# SparkFun_XBee_Development_Board.net
KiCad netlist of a schematic drawn in EAGLE
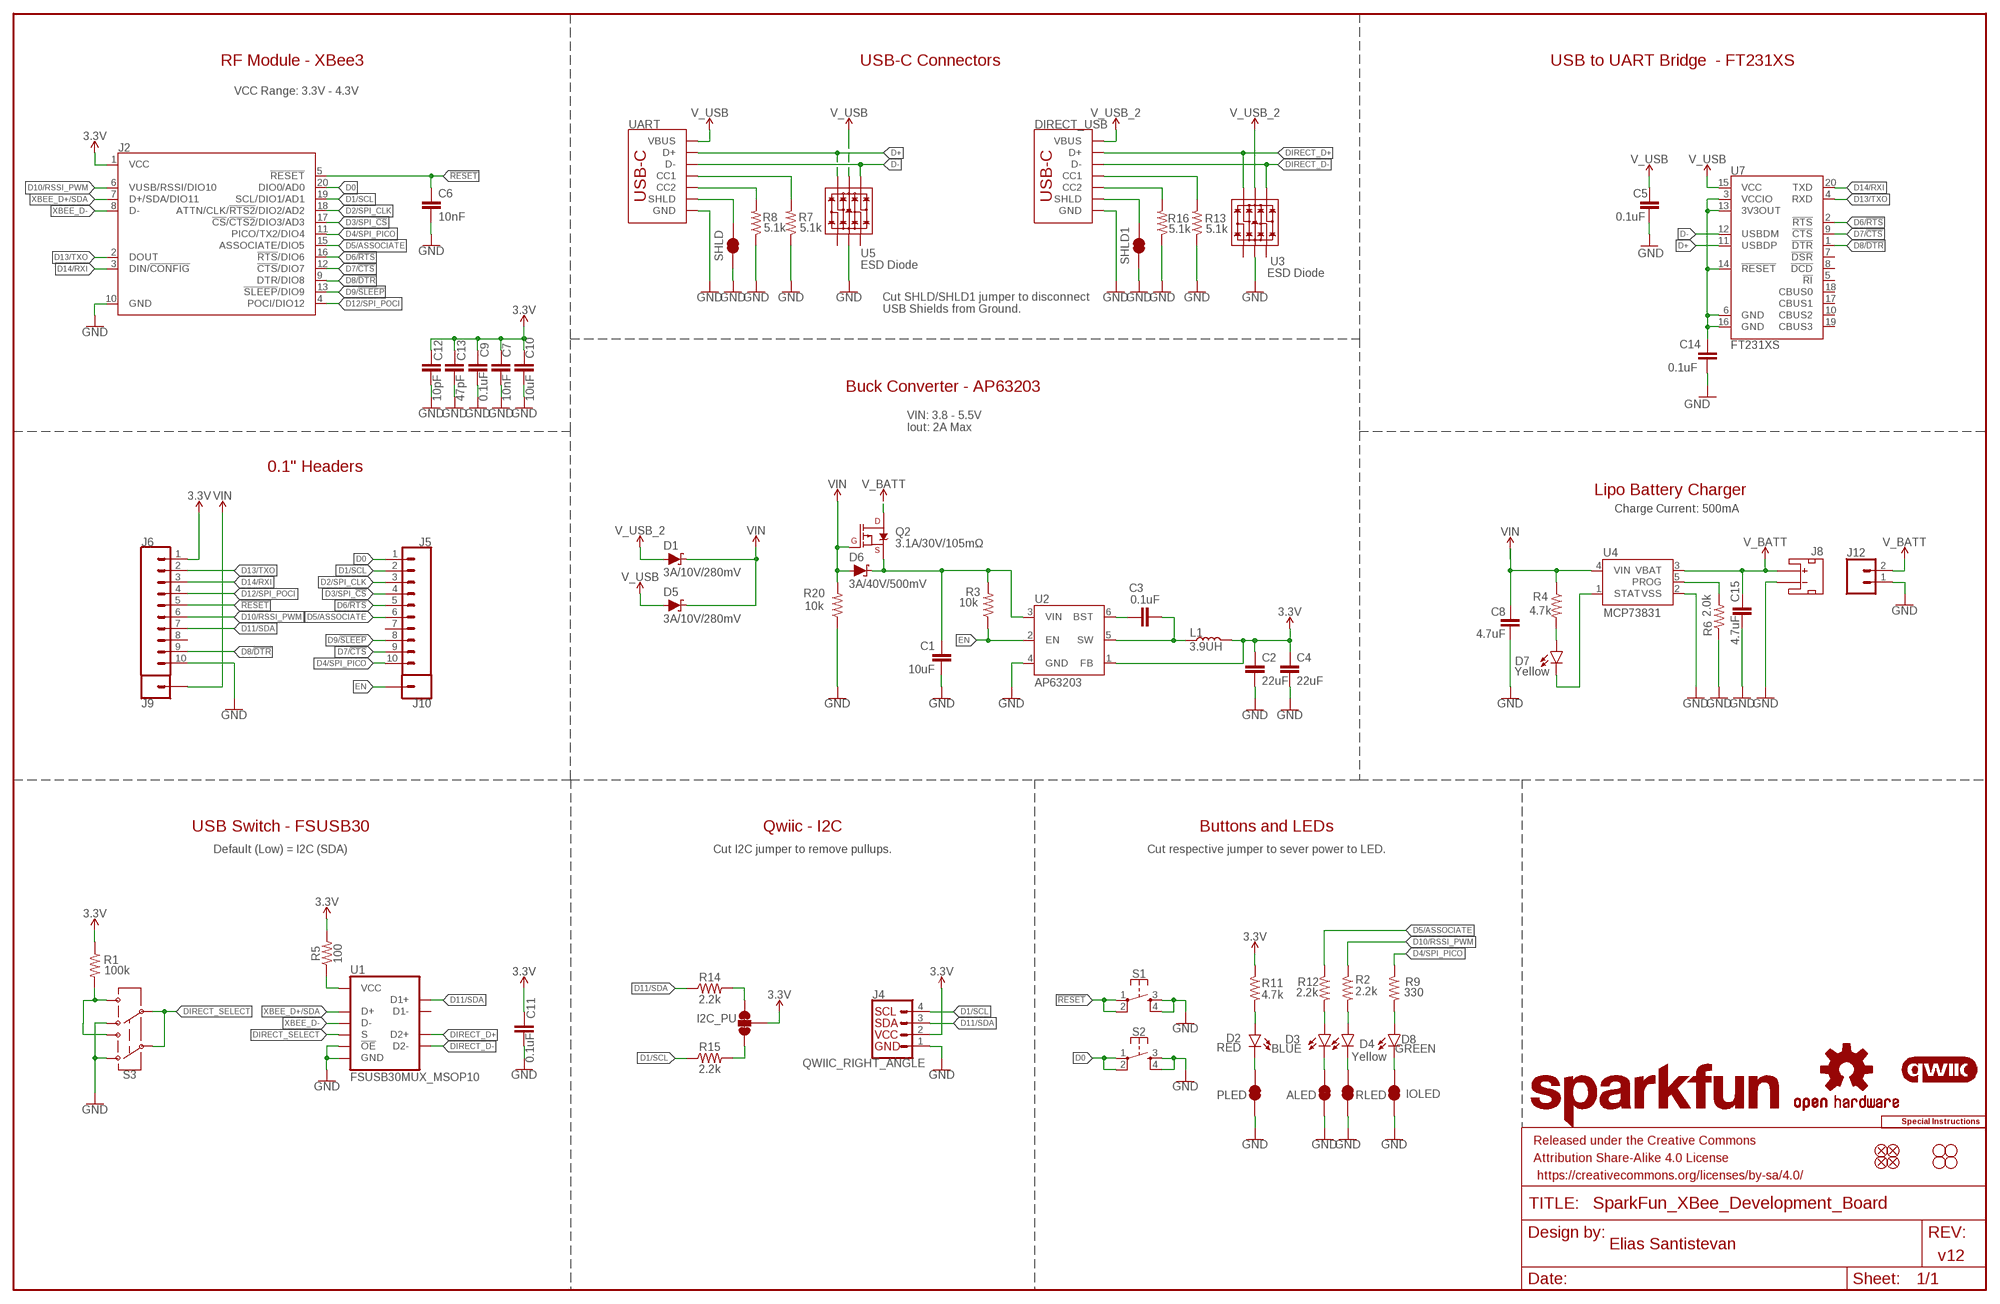
[diagram p0: schematic, sheet 1]

(export (version "E")
  (design (tool "Eeschema 10.0.6"))
  (components
    (comp (ref "ALED")
      (value "JUMPER-SMT_2_NC_TRACE_SILK")
      (footprint "eagle-import:SMT-JUMPER_2_NC_TRACE_SILK")
      (libsource (lib "eagle-import") (part "JUMPER-SMT_2_NC_TRACE_SILK"))
    )
    (comp (ref "C1")
      (value "10uF")
      (footprint "eagle-import:1210")
      (libsource (lib "eagle-import") (part "10UF-1210-50V-20%"))
    )
    (comp (ref "C2")
      (value "22uF")
      (footprint "eagle-import:0603")
      (libsource (lib "eagle-import") (part "22UF-0603-6.3V-20%"))
    )
    (comp (ref "C3")
      (value "0.1uF")
      (footprint "eagle-import:0603")
      (libsource (lib "eagle-import") (part "0.1UF-0603-25V-5%"))
    )
    (comp (ref "C4")
      (value "22uF")
      (footprint "eagle-import:0603")
      (libsource (lib "eagle-import") (part "22UF-0603-6.3V-20%"))
    )
    (comp (ref "C5")
      (value "0.1uF")
      (footprint "eagle-import:0603")
      (libsource (lib "eagle-import") (part "0.1UF-0603-25V-(+80/-20%)"))
    )
    (comp (ref "C6")
      (value "10nF")
      (footprint "eagle-import:0603")
      (libsource (lib "eagle-import") (part "10NF-0603-50V-10%"))
    )
    (comp (ref "C7")
      (value "10nF")
      (footprint "eagle-import:0603")
      (libsource (lib "eagle-import") (part "10NF-0603-50V-10%"))
    )
    (comp (ref "C8")
      (value "4.7uF")
      (footprint "eagle-import:0603")
      (libsource (lib "eagle-import") (part "4.7UF-0603-6.3V-(10%)"))
    )
    (comp (ref "C9")
      (value "0.1uF")
      (footprint "eagle-import:0603")
      (libsource (lib "eagle-import") (part "0.1UF-0603-25V-(+80/-20%)"))
    )
    (comp (ref "C10")
      (value "10uF")
      (footprint "eagle-import:0603")
      (libsource (lib "eagle-import") (part "10UF-0603-6.3V-20%"))
    )
    (comp (ref "C11")
      (value "0.1uF")
      (footprint "eagle-import:0603")
      (libsource (lib "eagle-import") (part "0.1UF-0603-25V-(+80/-20%)"))
    )
    (comp (ref "C12")
      (value "10pF")
      (footprint "eagle-import:0603")
      (libsource (lib "eagle-import") (part "10PF-0603-50V-5%"))
    )
    (comp (ref "C13")
      (value "47pF")
      (footprint "eagle-import:0603")
      (libsource (lib "eagle-import") (part "47PF-0603-50V-5%"))
    )
    (comp (ref "C14")
      (value "0.1uF")
      (footprint "eagle-import:0603")
      (libsource (lib "eagle-import") (part "0.1UF-0603-25V-(+80/-20%)"))
    )
    (comp (ref "C15")
      (value "4.7uF")
      (footprint "eagle-import:0603")
      (libsource (lib "eagle-import") (part "4.7UF-0603-35V-(20%)"))
    )
    (comp (ref "D1")
      (value "3A/10V/280mV")
      (footprint "eagle-import:SOD-323")
      (libsource (lib "eagle-import") (part "DIODE-SCHOTTKY-BAT60A"))
    )
    (comp (ref "D2")
      (value "RED")
      (footprint "eagle-import:LED-0603")
      (libsource (lib "eagle-import") (part "LED-RED_0603-KB"))
    )
    (comp (ref "D3")
      (value "BLUE")
      (footprint "eagle-import:LED-0603")
      (libsource (lib "eagle-import") (part "LED-BLUE0603"))
    )
    (comp (ref "D4")
      (value "Yellow")
      (footprint "eagle-import:LED-0603")
      (libsource (lib "eagle-import") (part "LED-YELLOW0603"))
    )
    (comp (ref "D5")
      (value "3A/10V/280mV")
      (footprint "eagle-import:SOD-323")
      (libsource (lib "eagle-import") (part "DIODE-SCHOTTKY-BAT60A"))
    )
    (comp (ref "D6")
      (value "3A/40V/500mV")
      (footprint "eagle-import:SMA-DIODE")
      (libsource (lib "eagle-import") (part "DIODE-SCHOTTKY-B340A"))
    )
    (comp (ref "D7")
      (value "Yellow")
      (footprint "eagle-import:LED-0603")
      (libsource (lib "eagle-import") (part "LED-YELLOW0603"))
    )
    (comp (ref "D8")
      (value "GREEN")
      (footprint "eagle-import:LED-0603")
      (libsource (lib "eagle-import") (part "LED-GREEN0603"))
    )
    (comp (ref "DIRECT_USB")
      (value "USB Female Type C Connector")
      (footprint "eagle-import:USB-C-16P-4LAYER-ISOLATED")
      (libsource (lib "eagle-import") (part "USB_C_4-LAYER-ISOLATED"))
    )
    (comp (ref "FD1")
      (value "FIDUCIAL1X2")
      (footprint "eagle-import:FIDUCIAL-1X2")
      (libsource (lib "eagle-import") (part "FIDUCIAL1X2"))
    )
    (comp (ref "FD2")
      (value "FIDUCIAL1X2")
      (footprint "eagle-import:FIDUCIAL-1X2")
      (libsource (lib "eagle-import") (part "FIDUCIAL1X2"))
    )
    (comp (ref "FD3")
      (value "FIDUCIAL1X2")
      (footprint "eagle-import:FIDUCIAL-1X2")
      (libsource (lib "eagle-import") (part "FIDUCIAL1X2"))
    )
    (comp (ref "FD4")
      (value "FIDUCIAL1X2")
      (footprint "eagle-import:FIDUCIAL-1X2")
      (libsource (lib "eagle-import") (part "FIDUCIAL1X2"))
    )
    (comp (ref "FRAME1")
      (value "FRAME-LEDGER")
      (footprint "eagle-import:CREATIVE_COMMONS")
      (libsource (lib "eagle-import") (part "FRAME-LEDGER"))
    )
    (comp (ref "H1")
      (value "STAND-OFFTIGHT")
      (footprint "eagle-import:STAND-OFF-TIGHT")
      (libsource (lib "eagle-import") (part "STAND-OFFTIGHT"))
    )
    (comp (ref "H2")
      (value "STAND-OFFTIGHT")
      (footprint "eagle-import:STAND-OFF-TIGHT")
      (libsource (lib "eagle-import") (part "STAND-OFFTIGHT"))
    )
    (comp (ref "H3")
      (value "STAND-OFFTIGHT")
      (footprint "eagle-import:STAND-OFF-TIGHT")
      (libsource (lib "eagle-import") (part "STAND-OFFTIGHT"))
    )
    (comp (ref "H4")
      (value "STAND-OFFTIGHT")
      (footprint "eagle-import:STAND-OFF-TIGHT")
      (libsource (lib "eagle-import") (part "STAND-OFFTIGHT"))
    )
    (comp (ref "I2C_PU")
      (value "JUMPER-SMT_3_2-NC_TRACE_SILK")
      (footprint "eagle-import:SMT-JUMPER_3_2-NC_TRACE_SILK")
      (libsource (lib "eagle-import") (part "JUMPER-SMT_3_2-NC_TRACE_SILK"))
    )
    (comp (ref "IOLED")
      (value "JUMPER-SMT_2_NC_TRACE_SILK")
      (footprint "eagle-import:SMT-JUMPER_2_NC_TRACE_SILK")
      (libsource (lib "eagle-import") (part "JUMPER-SMT_2_NC_TRACE_SILK"))
    )
    (comp (ref "J2")
      (value "XBEE_UPDATEXBEE_SMD")
      (footprint "eagle-import:XBEE3-SMD")
      (libsource (lib "eagle-import") (part "XBEE_UPDATEXBEE_SMD"))
    )
    (comp (ref "J4")
      (value "QWIIC_RIGHT_ANGLE")
      (footprint "eagle-import:JST04_1MM_RA")
      (libsource (lib "eagle-import") (part "QWIIC_CONNECTORJS-1MM"))
    )
    (comp (ref "J5")
      (value "CONN_10NO_SILK_PTH_FEMALE")
      (footprint "eagle-import:1X10_NO_SILK")
      (libsource (lib "eagle-import") (part "CONN_10NO_SILK_PTH_FEMALE"))
    )
    (comp (ref "J6")
      (value "CONN_10NO_SILK_PTH_FEMALE")
      (footprint "eagle-import:1X10_NO_SILK")
      (libsource (lib "eagle-import") (part "CONN_10NO_SILK_PTH_FEMALE"))
    )
    (comp (ref "J8")
      (value "JST_2MM_MALE")
      (footprint "eagle-import:JST-2-SMD")
      (libsource (lib "eagle-import") (part "JST_2MM_MALE"))
    )
    (comp (ref "J9")
      (value "CONN_01PTH_NO_SILK_STAND")
      (footprint "eagle-import:1X01_NO_SILK_STAND")
      (libsource (lib "eagle-import") (part "CONN_01PTH_NO_SILK_STAND"))
    )
    (comp (ref "J10")
      (value "CONN_01PTH_NO_SILK_STAND")
      (footprint "eagle-import:1X01_NO_SILK_STAND")
      (libsource (lib "eagle-import") (part "CONN_01PTH_NO_SILK_STAND"))
    )
    (comp (ref "J12")
      (value "CONN_021X02_NO_SILK")
      (footprint "eagle-import:1X02_NO_SILK")
      (libsource (lib "eagle-import") (part "CONN_021X02_NO_SILK"))
    )
    (comp (ref "L1")
      (value "3.9UH")
      (footprint "eagle-import:INDUCTOR_3.9UH")
      (libsource (lib "eagle-import") (part "3.9UH"))
    )
    (comp (ref "LOGO1")
      (value "SFE_LOGO_NAME.2_INCH")
      (footprint "eagle-import:SFE_LOGO_NAME_.2")
      (libsource (lib "eagle-import") (part "SFE_LOGO_NAME.2_INCH"))
    )
    (comp (ref "LOGO2")
      (value "OSHW-LOGOS")
      (footprint "eagle-import:OSHW-LOGO-S")
      (libsource (lib "eagle-import") (part "OSHW-LOGOS"))
    )
    (comp (ref "LOGO3")
      (value "QWIIC_LOGO_5MM")
      (footprint "eagle-import:QWIIC_5MM")
      (libsource (lib "eagle-import") (part "QWIIC_LOGO_5MM"))
    )
    (comp (ref "LOGO5")
      (value "SPECIAL_INSTRUCTIONS-ORDERING")
      (footprint "eagle-import:ORDERING_INSTRUCTIONS")
      (libsource (lib "eagle-import") (part "SPECIAL_INSTRUCTIONS-ORDERING"))
    )
    (comp (ref "PLED")
      (value "JUMPER-SMT_2_NC_TRACE_SILK")
      (footprint "eagle-import:SMT-JUMPER_2_NC_TRACE_SILK")
      (libsource (lib "eagle-import") (part "JUMPER-SMT_2_NC_TRACE_SILK"))
    )
    (comp (ref "Q2")
      (value "3.1A/30V/105mΩ")
      (footprint "eagle-import:SOT23-3")
      (libsource (lib "eagle-import") (part "MOSFET_PCH-DMG2307L"))
    )
    (comp (ref "R1")
      (value "100k")
      (footprint "eagle-import:0603")
      (libsource (lib "eagle-import") (part "100KOHM-0603-1/10W-1%"))
    )
    (comp (ref "R2")
      (value "2.2k")
      (footprint "eagle-import:0603")
      (libsource (lib "eagle-import") (part "2.2KOHM-0603-1/10W-1%"))
    )
    (comp (ref "R3")
      (value "10k")
      (footprint "eagle-import:0603")
      (libsource (lib "eagle-import") (part "10KOHM-0603-1/10W-1%"))
    )
    (comp (ref "R4")
      (value "4.7k")
      (footprint "eagle-import:0603")
      (libsource (lib "eagle-import") (part "4.7KOHM-0603-1/10W-1%"))
    )
    (comp (ref "R5")
      (value "100")
      (footprint "eagle-import:0603")
      (libsource (lib "eagle-import") (part "100OHM-0603-1/10W-1%"))
    )
    (comp (ref "R6")
      (value "2.0k")
      (footprint "eagle-import:0603")
      (libsource (lib "eagle-import") (part "2.0KOHM-0603-1/10W-5%"))
    )
    (comp (ref "R7")
      (value "5.1k")
      (footprint "eagle-import:0603")
      (libsource (lib "eagle-import") (part "5.1KOHM5.1KOHM-0603-1/10W-1%"))
    )
    (comp (ref "R8")
      (value "5.1k")
      (footprint "eagle-import:0603")
      (libsource (lib "eagle-import") (part "5.1KOHM5.1KOHM-0603-1/10W-1%"))
    )
    (comp (ref "R9")
      (value "330")
      (footprint "eagle-import:0603")
      (libsource (lib "eagle-import") (part "330OHM-0603-1/10W-1%"))
    )
    (comp (ref "R11")
      (value "4.7k")
      (footprint "eagle-import:0603")
      (libsource (lib "eagle-import") (part "4.7KOHM-0603-1/10W-1%"))
    )
    (comp (ref "R12")
      (value "2.2k")
      (footprint "eagle-import:0603")
      (libsource (lib "eagle-import") (part "2.2KOHM-0603-1/10W-1%"))
    )
    (comp (ref "R13")
      (value "5.1k")
      (footprint "eagle-import:0603")
      (libsource (lib "eagle-import") (part "5.1KOHM5.1KOHM-0603-1/10W-1%"))
    )
    (comp (ref "R14")
      (value "2.2k")
      (footprint "eagle-import:0603")
      (libsource (lib "eagle-import") (part "2.2KOHM-0603-1/10W-1%"))
    )
    (comp (ref "R15")
      (value "2.2k")
      (footprint "eagle-import:0603")
      (libsource (lib "eagle-import") (part "2.2KOHM-0603-1/10W-1%"))
    )
    (comp (ref "R16")
      (value "5.1k")
      (footprint "eagle-import:0603")
      (libsource (lib "eagle-import") (part "5.1KOHM5.1KOHM-0603-1/10W-1%"))
    )
    (comp (ref "R20")
      (value "10k")
      (footprint "eagle-import:0603")
      (libsource (lib "eagle-import") (part "10KOHM-0603-1/10W-1%"))
    )
    (comp (ref "RLED")
      (value "JUMPER-SMT_2_NC_TRACE_SILK")
      (footprint "eagle-import:SMT-JUMPER_2_NC_TRACE_SILK")
      (libsource (lib "eagle-import") (part "JUMPER-SMT_2_NC_TRACE_SILK"))
    )
    (comp (ref "S1")
      (value "MOMENTARY-SWITCH-SPST-2-SMD-5.2MM-TALL")
      (footprint "eagle-import:TACTILE_SWITCH_SMD_5.2MM")
      (libsource (lib "eagle-import") (part "MOMENTARY-SWITCH-SPST-2-SMD-5.2MM-TALL"))
    )
    (comp (ref "S2")
      (value "MOMENTARY-SWITCH-SPST-2-SMD-5.2MM-TALL")
      (footprint "eagle-import:TACTILE_SWITCH_SMD_5.2MM")
      (libsource (lib "eagle-import") (part "MOMENTARY-SWITCH-SPST-2-SMD-5.2MM-TALL"))
    )
    (comp (ref "S3")
      (value "SWITCH-DPDT-SMD-AYZ0202")
      (footprint "eagle-import:SWITCH_DPDT_SMD_AYZ0202")
      (libsource (lib "eagle-import") (part "SWITCH-DPDT-SMD-AYZ0202"))
    )
    (comp (ref "SHLD")
      (value "JUMPER-SMT_2_NC_TRACE_SILK")
      (footprint "eagle-import:SMT-JUMPER_2_NC_TRACE_SILK")
      (libsource (lib "eagle-import") (part "JUMPER-SMT_2_NC_TRACE_SILK"))
    )
    (comp (ref "SHLD1")
      (value "JUMPER-SMT_2_NC_TRACE_SILK")
      (footprint "eagle-import:SMT-JUMPER_2_NC_TRACE_SILK")
      (libsource (lib "eagle-import") (part "JUMPER-SMT_2_NC_TRACE_SILK"))
    )
    (comp (ref "U1")
      (value "FSUSB30MUX_MSOP10")
      (footprint "eagle-import:MSOP10")
      (libsource (lib "eagle-import") (part "FSUSB30MUX_MSOP10"))
    )
    (comp (ref "U2")
      (value "AP63203")
      (footprint "eagle-import:SOT23-6")
      (libsource (lib "eagle-import") (part "AP63203"))
    )
    (comp (ref "U3")
      (value "ESD Diode")
      (footprint "eagle-import:SOT-23-6")
      (libsource (lib "eagle-import") (part "TVS_DIODE_ARRAY_DT1042-04SO-7"))
    )
    (comp (ref "U4")
      (value "MCP73831")
      (footprint "eagle-import:SOT23-5")
      (libsource (lib "eagle-import") (part "MCP73831"))
    )
    (comp (ref "U5")
      (value "ESD Diode")
      (footprint "eagle-import:SOT-23-6")
      (libsource (lib "eagle-import") (part "TVS_DIODE_ARRAY_DT1042-04SO-7"))
    )
    (comp (ref "U7")
      (value "FT231XS")
      (footprint "eagle-import:SSOP20_L")
      (libsource (lib "eagle-import") (part "FT231XS"))
    )
    (comp (ref "UART")
      (value "USB Female Type C Connector")
      (footprint "eagle-import:USB-C-16P-4LAYER-ISOLATED")
      (libsource (lib "eagle-import") (part "USB_C_4-LAYER-ISOLATED"))
    )
  )
  (nets
    (net (code "1") (name "/D3{slash}SPI_~{CS}") (class "Default")
      (node (ref "J2") (pin "17") (pinfunction "~{CS}/~{CTS2}/DIO3/AD3_17") (pintype "bidirectional"))
      (node (ref "J5") (pin "4") (pinfunction "4_4") (pintype "passive"))
    )
    (net (code "2") (name "/D6{slash}~{RTS}") (class "Default")
      (node (ref "J2") (pin "16") (pinfunction "~{RTS}/DIO6_16") (pintype "input"))
      (node (ref "J5") (pin "5") (pinfunction "5_5") (pintype "passive"))
      (node (ref "U7") (pin "2") (pinfunction "~{RTS}_2") (pintype "bidirectional"))
    )
    (net (code "3") (name "/D7{slash}~{CTS}") (class "Default")
      (node (ref "J2") (pin "12") (pinfunction "~{CTS}/DIO7_12") (pintype "output"))
      (node (ref "J5") (pin "9") (pinfunction "9_9") (pintype "passive"))
      (node (ref "U7") (pin "9") (pinfunction "~{CTS}_9") (pintype "bidirectional"))
    )
    (net (code "4") (name "/D8{slash}~{DTR}") (class "Default")
      (node (ref "J2") (pin "9") (pinfunction "DTR/DIO8_9") (pintype "bidirectional"))
      (node (ref "J6") (pin "9") (pinfunction "9_9") (pintype "passive"))
      (node (ref "U7") (pin "1") (pinfunction "~{DTR}_1") (pintype "bidirectional"))
    )
    (net (code "5") (name "/D9{slash}~{SLEEP}") (class "Default")
      (node (ref "J2") (pin "13") (pinfunction "~{SLEEP}/DIO9_13") (pintype "bidirectional"))
      (node (ref "J5") (pin "8") (pinfunction "8_8") (pintype "passive"))
    )
    (net (code "6") (name "/~{RESET}") (class "Default")
      (node (ref "C6") (pin "1") (pinfunction "1_1") (pintype "passive"))
      (node (ref "J2") (pin "5") (pinfunction "~{RESET}_5") (pintype "input"))
      (node (ref "J6") (pin "5") (pinfunction "5_5") (pintype "passive"))
      (node (ref "S1") (pin "1") (pinfunction "1_1") (pintype "passive"))
      (node (ref "S1") (pin "2") (pinfunction "2_2") (pintype "passive"))
    )
    (net (code "7") (name "3.3V") (class "Default")
      (node (ref "C10") (pin "1") (pinfunction "1_1") (pintype "passive"))
      (node (ref "C11") (pin "1") (pinfunction "1_1") (pintype "passive"))
      (node (ref "C12") (pin "1") (pinfunction "1_1") (pintype "passive"))
      (node (ref "C13") (pin "1") (pinfunction "1_1") (pintype "passive"))
      (node (ref "C2") (pin "1") (pinfunction "1_1") (pintype "passive"))
      (node (ref "C4") (pin "1") (pinfunction "1_1") (pintype "passive"))
      (node (ref "C7") (pin "1") (pinfunction "1_1") (pintype "passive"))
      (node (ref "C9") (pin "1") (pinfunction "1_1") (pintype "passive"))
      (node (ref "I2C_PU") (pin "2") (pinfunction "2_2") (pintype "passive"))
      (node (ref "J2") (pin "1") (pinfunction "VCC_1") (pintype "power_in"))
      (node (ref "J4") (pin "2") (pinfunction "2_2") (pintype "power_in"))
      (node (ref "J6") (pin "1") (pinfunction "1_1") (pintype "passive"))
      (node (ref "L1") (pin "P$2") (pinfunction "2_P$2") (pintype "passive"))
      (node (ref "R1") (pin "1") (pinfunction "1_1") (pintype "passive"))
      (node (ref "R11") (pin "1") (pinfunction "1_1") (pintype "passive"))
      (node (ref "R5") (pin "2") (pinfunction "2_2") (pintype "passive"))
      (node (ref "U2") (pin "1") (pinfunction "FB_1") (pintype "bidirectional"))
    )
    (net (code "8") (name "D+") (class "Default")
      (node (ref "U5") (pin "6") (pinfunction "IO4_6") (pintype "bidirectional"))
      (node (ref "U7") (pin "11") (pinfunction "USBDP_11") (pintype "bidirectional"))
      (node (ref "UART") (pin "A6") (pinfunction "D+_A6") (pintype "bidirectional"))
      (node (ref "UART") (pin "B6") (pinfunction "D+_B6") (pintype "bidirectional"))
    )
    (net (code "9") (name "D-") (class "Default")
      (node (ref "U5") (pin "4") (pinfunction "IO3_4") (pintype "bidirectional"))
      (node (ref "U7") (pin "12") (pinfunction "USBDM_12") (pintype "bidirectional"))
      (node (ref "UART") (pin "A7") (pinfunction "D-_A7") (pintype "bidirectional"))
      (node (ref "UART") (pin "B7") (pinfunction "D-_B7") (pintype "bidirectional"))
    )
    (net (code "10") (name "D0") (class "Default")
      (node (ref "J2") (pin "20") (pinfunction "DIO0/AD0_20") (pintype "bidirectional"))
      (node (ref "J5") (pin "1") (pinfunction "1_1") (pintype "passive"))
      (node (ref "S2") (pin "1") (pinfunction "1_1") (pintype "passive"))
      (node (ref "S2") (pin "2") (pinfunction "2_2") (pintype "passive"))
    )
    (net (code "11") (name "D1{slash}SCL") (class "Default")
      (node (ref "J2") (pin "19") (pinfunction "SCL/DIO1/AD1_19") (pintype "bidirectional"))
      (node (ref "J4") (pin "4") (pinfunction "4_4") (pintype "passive"))
      (node (ref "J5") (pin "2") (pinfunction "2_2") (pintype "passive"))
      (node (ref "R15") (pin "1") (pinfunction "1_1") (pintype "passive"))
    )
    (net (code "12") (name "D2{slash}SPI_CLK") (class "Default")
      (node (ref "J2") (pin "18") (pinfunction "ATTN/CLK/~{RTS2}/DIO2/AD2_18") (pintype "bidirectional"))
      (node (ref "J5") (pin "3") (pinfunction "3_3") (pintype "passive"))
    )
    (net (code "13") (name "D4{slash}SPI_PICO") (class "Default")
      (node (ref "J2") (pin "11") (pinfunction "PICO/TX2/DIO4_11") (pintype "bidirectional"))
      (node (ref "J5") (pin "10") (pinfunction "10_10") (pintype "passive"))
      (node (ref "R9") (pin "1") (pinfunction "1_1") (pintype "passive"))
    )
    (net (code "14") (name "D5{slash}ASSOCIATE") (class "Default")
      (node (ref "J2") (pin "15") (pinfunction "ASSOCIATE/DIO5_15") (pintype "bidirectional"))
      (node (ref "J5") (pin "6") (pinfunction "6_6") (pintype "passive"))
      (node (ref "R12") (pin "1") (pinfunction "1_1") (pintype "passive"))
    )
    (net (code "15") (name "D10{slash}RSSI_PWM") (class "Default")
      (node (ref "J2") (pin "6") (pinfunction "VUSB/RSSI/DIO10_6") (pintype "bidirectional"))
      (node (ref "J6") (pin "6") (pinfunction "6_6") (pintype "passive"))
      (node (ref "R2") (pin "1") (pinfunction "1_1") (pintype "passive"))
    )
    (net (code "16") (name "D11{slash}SDA") (class "Default")
      (node (ref "J4") (pin "3") (pinfunction "3_3") (pintype "passive"))
      (node (ref "J6") (pin "7") (pinfunction "7_7") (pintype "passive"))
      (node (ref "R14") (pin "1") (pinfunction "1_1") (pintype "passive"))
      (node (ref "U1") (pin "2") (pinfunction "D1+_2") (pintype "bidirectional"))
    )
    (net (code "17") (name "D12{slash}SPI_POCI") (class "Default")
      (node (ref "J2") (pin "4") (pinfunction "POCI/DIO12_4") (pintype "bidirectional"))
      (node (ref "J6") (pin "4") (pinfunction "4_4") (pintype "passive"))
    )
    (net (code "18") (name "D13{slash}TXO") (class "Default")
      (node (ref "J2") (pin "2") (pinfunction "DOUT_2") (pintype "output"))
      (node (ref "J6") (pin "2") (pinfunction "2_2") (pintype "passive"))
      (node (ref "U7") (pin "4") (pinfunction "RXD_4") (pintype "bidirectional"))
    )
    (net (code "19") (name "D14{slash}RXI") (class "Default")
      (node (ref "J2") (pin "3") (pinfunction "DIN/~{CONFIG}_3") (pintype "input"))
      (node (ref "J6") (pin "3") (pinfunction "3_3") (pintype "passive"))
      (node (ref "U7") (pin "20") (pinfunction "TXD_20") (pintype "bidirectional"))
    )
    (net (code "20") (name "DIRECT_D+") (class "Default")
      (node (ref "DIRECT_USB") (pin "A6") (pinfunction "D+_A6") (pintype "bidirectional"))
      (node (ref "DIRECT_USB") (pin "B6") (pinfunction "D+_B6") (pintype "bidirectional"))
      (node (ref "U1") (pin "3") (pinfunction "D2+_3") (pintype "bidirectional"))
      (node (ref "U3") (pin "6") (pinfunction "IO4_6") (pintype "bidirectional"))
    )
    (net (code "21") (name "DIRECT_D-") (class "Default")
      (node (ref "DIRECT_USB") (pin "A7") (pinfunction "D-_A7") (pintype "bidirectional"))
      (node (ref "DIRECT_USB") (pin "B7") (pinfunction "D-_B7") (pintype "bidirectional"))
      (node (ref "U1") (pin "7") (pinfunction "D2-_7") (pintype "bidirectional"))
      (node (ref "U3") (pin "4") (pinfunction "IO3_4") (pintype "bidirectional"))
    )
    (net (code "22") (name "DIRECT_SELECT") (class "Default")
      (node (ref "S3") (pin "2") (pinfunction "2_2") (pintype "bidirectional"))
      (node (ref "S3") (pin "5") (pinfunction "5_5") (pintype "bidirectional"))
      (node (ref "U1") (pin "1") (pinfunction "S_1") (pintype "bidirectional"))
    )
    (net (code "23") (name "EN") (class "Default")
      (node (ref "J10") (pin "1") (pinfunction "1_1") (pintype "passive"))
      (node (ref "R3") (pin "1") (pinfunction "1_1") (pintype "passive"))
      (node (ref "U2") (pin "2") (pinfunction "EN_2") (pintype "bidirectional"))
    )
    (net (code "24") (name "GND") (class "Default")
      (node (ref "ALED") (pin "1") (pinfunction "1_1") (pintype "passive"))
      (node (ref "C1") (pin "2") (pinfunction "2_2") (pintype "passive"))
      (node (ref "C10") (pin "2") (pinfunction "2_2") (pintype "passive"))
      (node (ref "C11") (pin "2") (pinfunction "2_2") (pintype "passive"))
      (node (ref "C12") (pin "2") (pinfunction "2_2") (pintype "passive"))
      (node (ref "C13") (pin "2") (pinfunction "2_2") (pintype "passive"))
      (node (ref "C14") (pin "2") (pinfunction "2_2") (pintype "passive"))
      (node (ref "C15") (pin "2") (pinfunction "2_2") (pintype "passive"))
      (node (ref "C2") (pin "2") (pinfunction "2_2") (pintype "passive"))
      (node (ref "C4") (pin "2") (pinfunction "2_2") (pintype "passive"))
      (node (ref "C5") (pin "2") (pinfunction "2_2") (pintype "passive"))
      (node (ref "C6") (pin "2") (pinfunction "2_2") (pintype "passive"))
      (node (ref "C7") (pin "2") (pinfunction "2_2") (pintype "passive"))
      (node (ref "C8") (pin "2") (pinfunction "2_2") (pintype "passive"))
      (node (ref "C9") (pin "2") (pinfunction "2_2") (pintype "passive"))
      (node (ref "DIRECT_USB") (pin "GND") (pinfunction "GND_GND") (pintype "bidirectional"))
      (node (ref "DIRECT_USB") (pin "GND2") (pinfunction "GND_GND2") (pintype "bidirectional"))
      (node (ref "IOLED") (pin "1") (pinfunction "1_1") (pintype "passive"))
      (node (ref "J12") (pin "1") (pinfunction "1_1") (pintype "passive"))
      (node (ref "J2") (pin "10") (pinfunction "GND_10") (pintype "power_in"))
      (node (ref "J4") (pin "1") (pinfunction "1_1") (pintype "power_in"))
      (node (ref "J6") (pin "10") (pinfunction "10_10") (pintype "passive"))
      (node (ref "J8") (pin "1") (pinfunction "-_1") (pintype "bidirectional"))
      (node (ref "PLED") (pin "1") (pinfunction "1_1") (pintype "passive"))
      (node (ref "R13") (pin "1") (pinfunction "1_1") (pintype "passive"))
      (node (ref "R16") (pin "1") (pinfunction "1_1") (pintype "passive"))
      (node (ref "R20") (pin "1") (pinfunction "1_1") (pintype "passive"))
      (node (ref "R6") (pin "1") (pinfunction "1_1") (pintype "passive"))
      (node (ref "R7") (pin "1") (pinfunction "1_1") (pintype "passive"))
      (node (ref "R8") (pin "1") (pinfunction "1_1") (pintype "passive"))
      (node (ref "RLED") (pin "1") (pinfunction "1_1") (pintype "passive"))
      (node (ref "S1") (pin "3") (pinfunction "3_3") (pintype "passive"))
      (node (ref "S1") (pin "4") (pinfunction "4_4") (pintype "passive"))
      (node (ref "S2") (pin "3") (pinfunction "3_3") (pintype "passive"))
      (node (ref "S2") (pin "4") (pinfunction "4_4") (pintype "passive"))
      (node (ref "S3") (pin "3") (pinfunction "3_3") (pintype "bidirectional"))
      (node (ref "S3") (pin "6") (pinfunction "6_6") (pintype "bidirectional"))
      (node (ref "SHLD") (pin "1") (pinfunction "1_1") (pintype "passive"))
      (node (ref "SHLD1") (pin "1") (pinfunction "1_1") (pintype "passive"))
      (node (ref "U1") (pin "5") (pinfunction "GND_5") (pintype "bidirectional"))
      (node (ref "U1") (pin "9") (pinfunction "~{OE}_9") (pintype "bidirectional"))
      (node (ref "U2") (pin "4") (pinfunction "GND_4") (pintype "bidirectional"))
      (node (ref "U3") (pin "2") (pinfunction "VSS_2") (pintype "bidirectional"))
      (node (ref "U4") (pin "2") (pinfunction "VSS_2") (pintype "power_in"))
      (node (ref "U5") (pin "2") (pinfunction "VSS_2") (pintype "bidirectional"))
      (node (ref "UART") (pin "GND") (pinfunction "GND_GND") (pintype "bidirectional"))
      (node (ref "UART") (pin "GND2") (pinfunction "GND_GND2") (pintype "bidirectional"))
    )
    (net (code "25") (name "Net-(ALED-Pad2)") (class "Default")
      (node (ref "ALED") (pin "2") (pinfunction "2_2") (pintype "passive"))
      (node (ref "D3") (pin "C") (pinfunction "C_C") (pintype "passive"))
    )
    (net (code "26") (name "Net-(D2-PadA)") (class "Default")
      (node (ref "D2") (pin "A") (pinfunction "A_A") (pintype "passive"))
      (node (ref "R11") (pin "2") (pinfunction "2_2") (pintype "passive"))
    )
    (net (code "27") (name "Net-(D2-PadC)") (class "Default")
      (node (ref "D2") (pin "C") (pinfunction "C_C") (pintype "passive"))
      (node (ref "PLED") (pin "2") (pinfunction "2_2") (pintype "passive"))
    )
    (net (code "28") (name "Net-(D3-PadA)") (class "Default")
      (node (ref "D3") (pin "A") (pinfunction "A_A") (pintype "passive"))
      (node (ref "R12") (pin "2") (pinfunction "2_2") (pintype "passive"))
    )
    (net (code "29") (name "Net-(D4-PadA)") (class "Default")
      (node (ref "D4") (pin "A") (pinfunction "A_A") (pintype "passive"))
      (node (ref "R2") (pin "2") (pinfunction "2_2") (pintype "passive"))
    )
    (net (code "30") (name "Net-(D4-PadC)") (class "Default")
      (node (ref "D4") (pin "C") (pinfunction "C_C") (pintype "passive"))
      (node (ref "RLED") (pin "2") (pinfunction "2_2") (pintype "passive"))
    )
    (net (code "31") (name "Net-(D7-PadA)") (class "Default")
      (node (ref "D7") (pin "A") (pinfunction "A_A") (pintype "passive"))
      (node (ref "R4") (pin "2") (pinfunction "2_2") (pintype "passive"))
    )
    (net (code "32") (name "Net-(D8-PadA)") (class "Default")
      (node (ref "D8") (pin "A") (pinfunction "A_A") (pintype "passive"))
      (node (ref "R9") (pin "2") (pinfunction "2_2") (pintype "passive"))
    )
    (net (code "33") (name "Net-(D8-PadC)") (class "Default")
      (node (ref "D8") (pin "C") (pinfunction "C_C") (pintype "passive"))
      (node (ref "IOLED") (pin "2") (pinfunction "2_2") (pintype "passive"))
    )
    (net (code "34") (name "Net-(DIRECT_USB-CC1)") (class "Default")
      (node (ref "DIRECT_USB") (pin "A5") (pinfunction "CC1_A5") (pintype "bidirectional"))
      (node (ref "R13") (pin "2") (pinfunction "2_2") (pintype "passive"))
    )
    (net (code "35") (name "Net-(DIRECT_USB-CC2)") (class "Default")
      (node (ref "DIRECT_USB") (pin "B5") (pinfunction "CC2_B5") (pintype "bidirectional"))
      (node (ref "R16") (pin "2") (pinfunction "2_2") (pintype "passive"))
    )
    (net (code "36") (name "Net-(DIRECT_USB-SHLD-PadSHLD1)") (class "Default")
      (node (ref "DIRECT_USB") (pin "SHLD1") (pinfunction "SHLD_SHLD1") (pintype "bidirectional"))
      (node (ref "DIRECT_USB") (pin "SHLD2") (pinfunction "SHLD_SHLD2") (pintype "bidirectional"))
      (node (ref "DIRECT_USB") (pin "SHLD3") (pinfunction "SHLD_SHLD3") (pintype "bidirectional"))
      (node (ref "DIRECT_USB") (pin "SHLD4") (pinfunction "SHLD_SHLD4") (pintype "bidirectional"))
      (node (ref "DIRECT_USB") (pin "SHLD5") (pinfunction "SHLD_SHLD5") (pintype "bidirectional"))
      (node (ref "DIRECT_USB") (pin "SHLD6") (pinfunction "SHLD_SHLD6") (pintype "bidirectional"))
      (node (ref "DIRECT_USB") (pin "SHLD7") (pinfunction "SHLD_SHLD7") (pintype "bidirectional"))
      (node (ref "DIRECT_USB") (pin "SHLD8") (pinfunction "SHLD_SHLD8") (pintype "bidirectional"))
      (node (ref "SHLD1") (pin "2") (pinfunction "2_2") (pintype "passive"))
    )
    (net (code "37") (name "Net-(I2C_PU-Pad1)") (class "Default")
      (node (ref "I2C_PU") (pin "1") (pinfunction "1_1") (pintype "passive"))
      (node (ref "R15") (pin "2") (pinfunction "2_2") (pintype "passive"))
    )
    (net (code "38") (name "Net-(I2C_PU-Pad3)") (class "Default")
      (node (ref "I2C_PU") (pin "3") (pinfunction "3_3") (pintype "passive"))
      (node (ref "R14") (pin "2") (pinfunction "2_2") (pintype "passive"))
    )
    (net (code "39") (name "Net-(L1-1)") (class "Default")
      (node (ref "C3") (pin "2") (pinfunction "2_2") (pintype "passive"))
      (node (ref "L1") (pin "P$1") (pinfunction "1_P$1") (pintype "passive"))
      (node (ref "U2") (pin "5") (pinfunction "SW_5") (pintype "bidirectional"))
    )
    (net (code "40") (name "Net-(Q2-S)") (class "Default")
      (node (ref "C1") (pin "1") (pinfunction "1_1") (pintype "passive"))
      (node (ref "D6") (pin "C") (pinfunction "C_C") (pintype "passive"))
      (node (ref "Q2") (pin "2") (pinfunction "S_2") (pintype "bidirectional"))
      (node (ref "R3") (pin "2") (pinfunction "2_2") (pintype "passive"))
      (node (ref "U2") (pin "3") (pinfunction "VIN_3") (pintype "bidirectional"))
    )
    (net (code "41") (name "Net-(R1-Pad2)") (class "Default")
      (node (ref "R1") (pin "2") (pinfunction "2_2") (pintype "passive"))
      (node (ref "S3") (pin "1") (pinfunction "1_1") (pintype "bidirectional"))
      (node (ref "S3") (pin "4") (pinfunction "4_4") (pintype "bidirectional"))
    )
    (net (code "42") (name "Net-(SHLD-Pad2)") (class "Default")
      (node (ref "SHLD") (pin "2") (pinfunction "2_2") (pintype "passive"))
      (node (ref "UART") (pin "SHLD1") (pinfunction "SHLD_SHLD1") (pintype "bidirectional"))
      (node (ref "UART") (pin "SHLD2") (pinfunction "SHLD_SHLD2") (pintype "bidirectional"))
      (node (ref "UART") (pin "SHLD3") (pinfunction "SHLD_SHLD3") (pintype "bidirectional"))
      (node (ref "UART") (pin "SHLD4") (pinfunction "SHLD_SHLD4") (pintype "bidirectional"))
      (node (ref "UART") (pin "SHLD5") (pinfunction "SHLD_SHLD5") (pintype "bidirectional"))
      (node (ref "UART") (pin "SHLD6") (pinfunction "SHLD_SHLD6") (pintype "bidirectional"))
      (node (ref "UART") (pin "SHLD7") (pinfunction "SHLD_SHLD7") (pintype "bidirectional"))
      (node (ref "UART") (pin "SHLD8") (pinfunction "SHLD_SHLD8") (pintype "bidirectional"))
    )
    (net (code "43") (name "Net-(U1-VCC)") (class "Default")
      (node (ref "R5") (pin "1") (pinfunction "1_1") (pintype "passive"))
      (node (ref "U1") (pin "10") (pinfunction "VCC_10") (pintype "bidirectional"))
    )
    (net (code "44") (name "Net-(U2-BST)") (class "Default")
      (node (ref "C3") (pin "1") (pinfunction "1_1") (pintype "passive"))
      (node (ref "U2") (pin "6") (pinfunction "BST_6") (pintype "bidirectional"))
    )
    (net (code "45") (name "Net-(U4-PROG)") (class "Default")
      (node (ref "R6") (pin "2") (pinfunction "2_2") (pintype "passive"))
      (node (ref "U4") (pin "5") (pinfunction "PROG_5") (pintype "input"))
    )
    (net (code "46") (name "Net-(U4-STAT)") (class "Default")
      (node (ref "D7") (pin "C") (pinfunction "C_C") (pintype "passive"))
      (node (ref "U4") (pin "1") (pinfunction "STAT_1") (pintype "output"))
    )
    (net (code "47") (name "Net-(U7-3V3OUT)") (class "Default")
      (node (ref "C14") (pin "1") (pinfunction "1_1") (pintype "passive"))
      (node (ref "U7") (pin "13") (pinfunction "3V3OUT_13") (pintype "bidirectional"))
      (node (ref "U7") (pin "14") (pinfunction "~{RESET}_14") (pintype "bidirectional"))
      (node (ref "U7") (pin "16") (pinfunction "GND_16") (pintype "bidirectional"))
      (node (ref "U7") (pin "3") (pinfunction "VCCIO_3") (pintype "bidirectional"))
      (node (ref "U7") (pin "6") (pinfunction "GND_6") (pintype "bidirectional"))
    )
    (net (code "48") (name "Net-(UART-CC1)") (class "Default")
      (node (ref "R7") (pin "2") (pinfunction "2_2") (pintype "passive"))
      (node (ref "UART") (pin "A5") (pinfunction "CC1_A5") (pintype "bidirectional"))
    )
    (net (code "49") (name "Net-(UART-CC2)") (class "Default")
      (node (ref "R8") (pin "2") (pinfunction "2_2") (pintype "passive"))
      (node (ref "UART") (pin "B5") (pinfunction "CC2_B5") (pintype "bidirectional"))
    )
    (net (code "50") (name "VIN") (class "Default")
      (node (ref "C8") (pin "1") (pinfunction "1_1") (pintype "passive"))
      (node (ref "D1") (pin "C") (pinfunction "C_C") (pintype "passive"))
      (node (ref "D5") (pin "C") (pinfunction "C_C") (pintype "passive"))
      (node (ref "D6") (pin "A") (pinfunction "A_A") (pintype "passive"))
      (node (ref "J9") (pin "1") (pinfunction "1_1") (pintype "passive"))
      (node (ref "Q2") (pin "1") (pinfunction "G_1") (pintype "bidirectional"))
      (node (ref "R20") (pin "2") (pinfunction "2_2") (pintype "passive"))
      (node (ref "R4") (pin "1") (pinfunction "1_1") (pintype "passive"))
      (node (ref "U4") (pin "4") (pinfunction "VIN_4") (pintype "power_in"))
    )
    (net (code "51") (name "V_BATT") (class "Default")
      (node (ref "C15") (pin "1") (pinfunction "1_1") (pintype "passive"))
      (node (ref "J12") (pin "2") (pinfunction "2_2") (pintype "passive"))
      (node (ref "J8") (pin "2") (pinfunction "+_2") (pintype "bidirectional"))
      (node (ref "Q2") (pin "3") (pinfunction "D_3") (pintype "bidirectional"))
      (node (ref "U4") (pin "3") (pinfunction "VBAT_3") (pintype "power_in"))
    )
    (net (code "52") (name "V_USB") (class "Default")
      (node (ref "C5") (pin "1") (pinfunction "1_1") (pintype "passive"))
      (node (ref "D5") (pin "A") (pinfunction "A_A") (pintype "passive"))
      (node (ref "U5") (pin "5") (pinfunction "VCC_5") (pintype "bidirectional"))
      (node (ref "U7") (pin "15") (pinfunction "VCC_15") (pintype "bidirectional"))
      (node (ref "UART") (pin "VBUS1") (pinfunction "VBUS_VBUS1") (pintype "bidirectional"))
      (node (ref "UART") (pin "VBUS2") (pinfunction "VBUS_VBUS2") (pintype "bidirectional"))
    )
    (net (code "53") (name "V_USB_2") (class "Default")
      (node (ref "D1") (pin "A") (pinfunction "A_A") (pintype "passive"))
      (node (ref "DIRECT_USB") (pin "VBUS1") (pinfunction "VBUS_VBUS1") (pintype "bidirectional"))
      (node (ref "DIRECT_USB") (pin "VBUS2") (pinfunction "VBUS_VBUS2") (pintype "bidirectional"))
      (node (ref "U3") (pin "5") (pinfunction "VCC_5") (pintype "bidirectional"))
    )
    (net (code "54") (name "XBEE_D+{slash}SDA") (class "Default")
      (node (ref "J2") (pin "7") (pinfunction "D+/SDA/DIO11_7") (pintype "bidirectional"))
      (node (ref "U1") (pin "4") (pinfunction "D+_4") (pintype "bidirectional"))
    )
    (net (code "55") (name "XBEE_D-") (class "Default")
      (node (ref "J2") (pin "8") (pinfunction "D-_8") (pintype "bidirectional"))
      (node (ref "U1") (pin "6") (pinfunction "D-_6") (pintype "bidirectional"))
    )
    (net (code "56") (name "unconnected-(J5-Pad7)") (class "Default")
      (node (ref "J5") (pin "7") (pinfunction "7_7") (pintype "passive"))
    )
    (net (code "57") (name "unconnected-(J6-Pad8)") (class "Default")
      (node (ref "J6") (pin "8") (pinfunction "8_8") (pintype "passive"))
    )
    (net (code "58") (name "unconnected-(J8-PAD1-PadNC1)") (class "Default")
      (node (ref "J8") (pin "NC1") (pinfunction "PAD1_NC1") (pintype "bidirectional"))
    )
    (net (code "59") (name "unconnected-(J8-PAD2-PadNC2)") (class "Default")
      (node (ref "J8") (pin "NC2") (pinfunction "PAD2_NC2") (pintype "bidirectional"))
    )
    (net (code "60") (name "unconnected-(U1-D1--Pad8)") (class "Default")
      (node (ref "U1") (pin "8") (pinfunction "D1-_8") (pintype "bidirectional"))
    )
    (net (code "61") (name "unconnected-(U3-IO1-Pad1)") (class "Default")
      (node (ref "U3") (pin "1") (pinfunction "IO1_1") (pintype "bidirectional"))
    )
    (net (code "62") (name "unconnected-(U3-IO2-Pad3)") (class "Default")
      (node (ref "U3") (pin "3") (pinfunction "IO2_3") (pintype "bidirectional"))
    )
    (net (code "63") (name "unconnected-(U5-IO1-Pad1)") (class "Default")
      (node (ref "U5") (pin "1") (pinfunction "IO1_1") (pintype "bidirectional"))
    )
    (net (code "64") (name "unconnected-(U5-IO2-Pad3)") (class "Default")
      (node (ref "U5") (pin "3") (pinfunction "IO2_3") (pintype "bidirectional"))
    )
    (net (code "65") (name "unconnected-(U7-CBUS0-Pad18)") (class "Default")
      (node (ref "U7") (pin "18") (pinfunction "CBUS0_18") (pintype "bidirectional"))
    )
    (net (code "66") (name "unconnected-(U7-CBUS1-Pad17)") (class "Default")
      (node (ref "U7") (pin "17") (pinfunction "CBUS1_17") (pintype "bidirectional"))
    )
    (net (code "67") (name "unconnected-(U7-CBUS2-Pad10)") (class "Default")
      (node (ref "U7") (pin "10") (pinfunction "CBUS2_10") (pintype "bidirectional"))
    )
    (net (code "68") (name "unconnected-(U7-CBUS3-Pad19)") (class "Default")
      (node (ref "U7") (pin "19") (pinfunction "CBUS3_19") (pintype "bidirectional"))
    )
    (net (code "69") (name "unconnected-(U7-~{DCD}-Pad8)") (class "Default")
      (node (ref "U7") (pin "8") (pinfunction "~{DCD}_8") (pintype "bidirectional"))
    )
    (net (code "70") (name "unconnected-(U7-~{DSR}-Pad7)") (class "Default")
      (node (ref "U7") (pin "7") (pinfunction "~{DSR}_7") (pintype "bidirectional"))
    )
    (net (code "71") (name "unconnected-(U7-~{RI}-Pad5)") (class "Default")
      (node (ref "U7") (pin "5") (pinfunction "~{RI}_5") (pintype "bidirectional"))
    )
  )
)
